# APP_1_ADC_m.net
KiCad netlist of a schematic drawn in Altium Designer
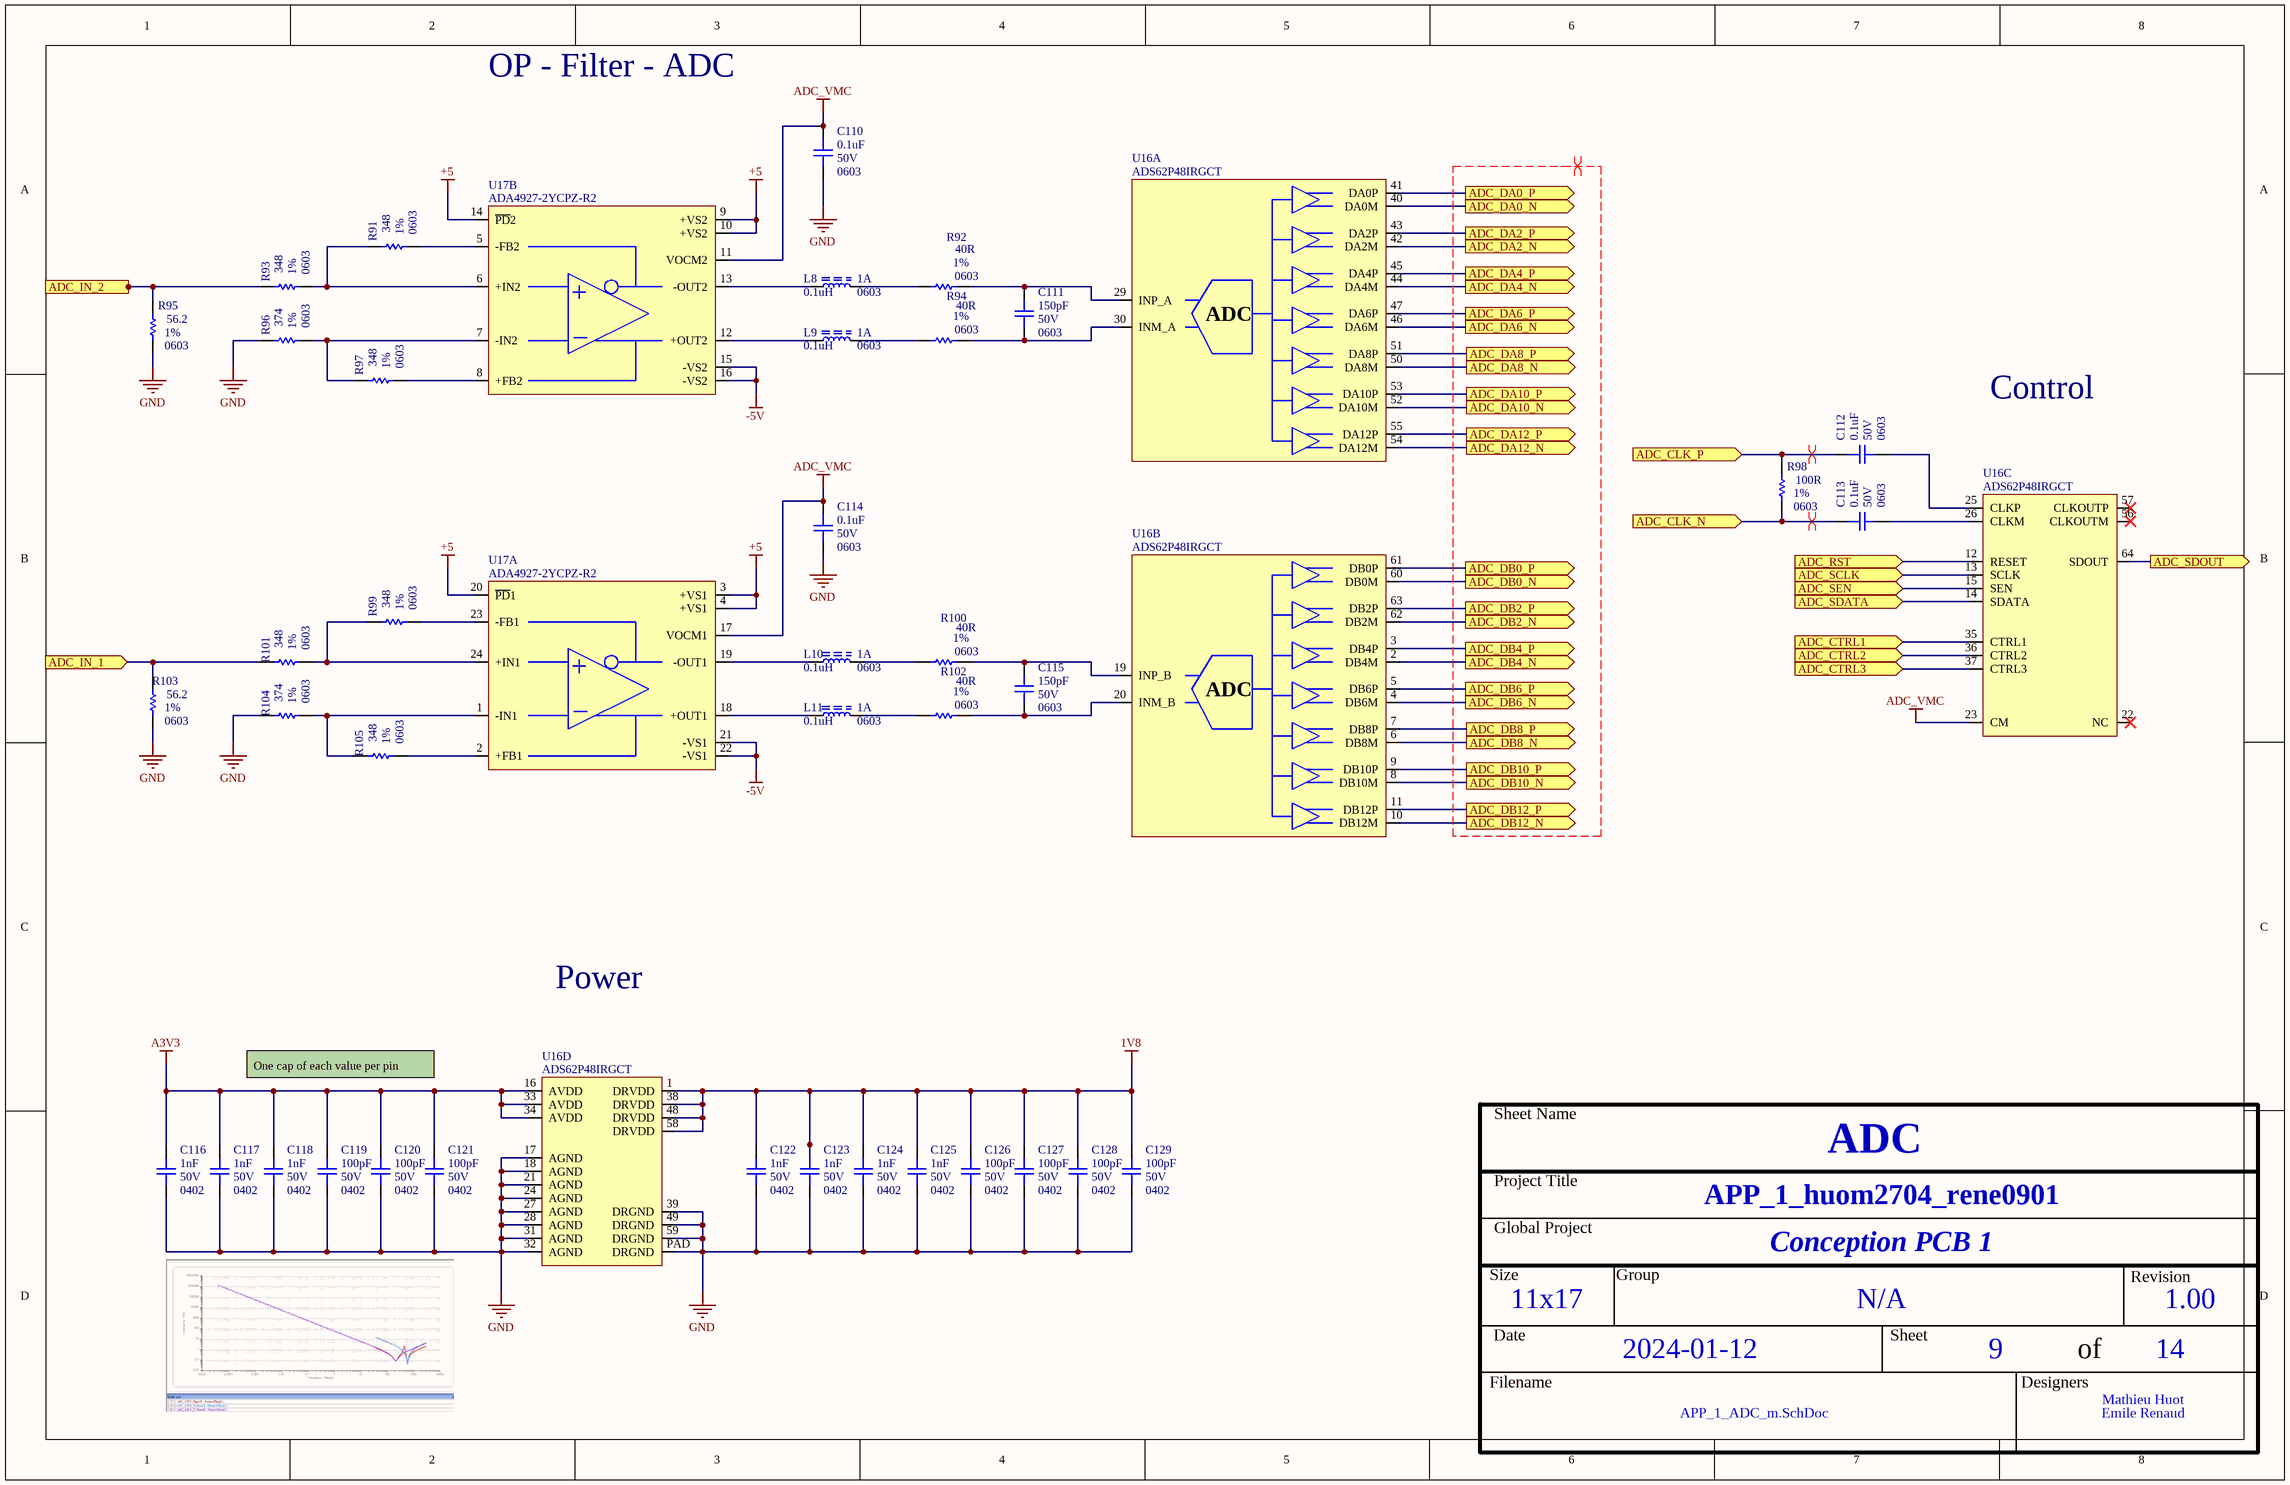
[diagram p0: APP_1_ADC_m.SchDoc]

(export (version "E")
  (design (tool "Eeschema 10.0.6"))
  (components
    (comp (ref "C110")
      (value "0.1uF")
      (footprint "CAP_0603")
      (description "CAP - 0603")
      (fields
        (field (name "VOLTAGE") "50V")
        (field (name "PACKAGE") "0603")
        (field (name "CREATEDBY") "Jonathan Bouchard")
      )
      (libsource (lib "S7CAS_LIB2023") (part "CAP - 0603"))
    )
    (comp (ref "C111")
      (value "150pF")
      (footprint "CAP_0603")
      (description "CAP - 0603")
      (fields
        (field (name "VOLTAGE") "50V")
        (field (name "PACKAGE") "0603")
        (field (name "CREATEDBY") "Jonathan Bouchard")
      )
      (libsource (lib "S7CAS_LIB2023") (part "CAP - 0603"))
    )
    (comp (ref "C112")
      (value "0.1uF")
      (footprint "CAP_0603")
      (description "CAP - 0603")
      (fields
        (field (name "VOLTAGE") "50V")
        (field (name "PACKAGE") "0603")
        (field (name "CREATEDBY") "Jonathan Bouchard")
      )
      (libsource (lib "S7CAS_LIB2023") (part "CAP - 0603"))
    )
    (comp (ref "C113")
      (value "0.1uF")
      (footprint "CAP_0603")
      (description "CAP - 0603")
      (fields
        (field (name "VOLTAGE") "50V")
        (field (name "PACKAGE") "0603")
        (field (name "CREATEDBY") "Jonathan Bouchard")
      )
      (libsource (lib "S7CAS_LIB2023") (part "CAP - 0603"))
    )
    (comp (ref "C114")
      (value "0.1uF")
      (footprint "CAP_0603")
      (description "CAP - 0603")
      (fields
        (field (name "VOLTAGE") "50V")
        (field (name "PACKAGE") "0603")
        (field (name "CREATEDBY") "Jonathan Bouchard")
      )
      (libsource (lib "S7CAS_LIB2023") (part "CAP - 0603"))
    )
    (comp (ref "C115")
      (value "150pF")
      (footprint "CAP_0603")
      (description "CAP - 0603")
      (fields
        (field (name "VOLTAGE") "50V")
        (field (name "PACKAGE") "0603")
        (field (name "CREATEDBY") "Jonathan Bouchard")
      )
      (libsource (lib "S7CAS_LIB2023") (part "CAP - 0603"))
    )
    (comp (ref "C116")
      (value "1nF")
      (footprint "CAP_0402")
      (description "CAP - 0402")
      (fields
        (field (name "VOLTAGE") "50V")
        (field (name "PACKAGE") "0402")
        (field (name "CREATEDBY") "Jonathan Bouchard")
      )
      (libsource (lib "S7CAS_LIB2023") (part "CAP - 0402"))
    )
    (comp (ref "C117")
      (value "1nF")
      (footprint "CAP_0402")
      (description "CAP - 0402")
      (fields
        (field (name "VOLTAGE") "50V")
        (field (name "PACKAGE") "0402")
        (field (name "CREATEDBY") "Jonathan Bouchard")
      )
      (libsource (lib "S7CAS_LIB2023") (part "CAP - 0402"))
    )
    (comp (ref "C118")
      (value "1nF")
      (footprint "CAP_0402")
      (description "CAP - 0402")
      (fields
        (field (name "VOLTAGE") "50V")
        (field (name "PACKAGE") "0402")
        (field (name "CREATEDBY") "Jonathan Bouchard")
      )
      (libsource (lib "S7CAS_LIB2023") (part "CAP - 0402"))
    )
    (comp (ref "C119")
      (value "100pF")
      (footprint "CAP_0402")
      (description "CAP - 0402")
      (fields
        (field (name "VOLTAGE") "50V")
        (field (name "PACKAGE") "0402")
        (field (name "CREATEDBY") "Jonathan Bouchard")
      )
      (libsource (lib "S7CAS_LIB2023") (part "CAP - 0402"))
    )
    (comp (ref "C120")
      (value "100pF")
      (footprint "CAP_0402")
      (description "CAP - 0402")
      (fields
        (field (name "VOLTAGE") "50V")
        (field (name "PACKAGE") "0402")
        (field (name "CREATEDBY") "Jonathan Bouchard")
      )
      (libsource (lib "S7CAS_LIB2023") (part "CAP - 0402"))
    )
    (comp (ref "C121")
      (value "100pF")
      (footprint "CAP_0402")
      (description "CAP - 0402")
      (fields
        (field (name "VOLTAGE") "50V")
        (field (name "PACKAGE") "0402")
        (field (name "CREATEDBY") "Jonathan Bouchard")
      )
      (libsource (lib "S7CAS_LIB2023") (part "CAP - 0402"))
    )
    (comp (ref "C122")
      (value "1nF")
      (footprint "CAP_0402")
      (description "CAP - 0402")
      (fields
        (field (name "VOLTAGE") "50V")
        (field (name "PACKAGE") "0402")
        (field (name "CREATEDBY") "Jonathan Bouchard")
      )
      (libsource (lib "S7CAS_LIB2023") (part "CAP - 0402"))
    )
    (comp (ref "C123")
      (value "1nF")
      (footprint "CAP_0402")
      (description "CAP - 0402")
      (fields
        (field (name "VOLTAGE") "50V")
        (field (name "PACKAGE") "0402")
        (field (name "CREATEDBY") "Jonathan Bouchard")
      )
      (libsource (lib "S7CAS_LIB2023") (part "CAP - 0402"))
    )
    (comp (ref "C124")
      (value "1nF")
      (footprint "CAP_0402")
      (description "CAP - 0402")
      (fields
        (field (name "VOLTAGE") "50V")
        (field (name "PACKAGE") "0402")
        (field (name "CREATEDBY") "Jonathan Bouchard")
      )
      (libsource (lib "S7CAS_LIB2023") (part "CAP - 0402"))
    )
    (comp (ref "C125")
      (value "1nF")
      (footprint "CAP_0402")
      (description "CAP - 0402")
      (fields
        (field (name "VOLTAGE") "50V")
        (field (name "PACKAGE") "0402")
        (field (name "CREATEDBY") "Jonathan Bouchard")
      )
      (libsource (lib "S7CAS_LIB2023") (part "CAP - 0402"))
    )
    (comp (ref "C126")
      (value "100pF")
      (footprint "CAP_0402")
      (description "CAP - 0402")
      (fields
        (field (name "VOLTAGE") "50V")
        (field (name "PACKAGE") "0402")
        (field (name "CREATEDBY") "Jonathan Bouchard")
      )
      (libsource (lib "S7CAS_LIB2023") (part "CAP - 0402"))
    )
    (comp (ref "C127")
      (value "100pF")
      (footprint "CAP_0402")
      (description "CAP - 0402")
      (fields
        (field (name "VOLTAGE") "50V")
        (field (name "PACKAGE") "0402")
        (field (name "CREATEDBY") "Jonathan Bouchard")
      )
      (libsource (lib "S7CAS_LIB2023") (part "CAP - 0402"))
    )
    (comp (ref "C128")
      (value "100pF")
      (footprint "CAP_0402")
      (description "CAP - 0402")
      (fields
        (field (name "VOLTAGE") "50V")
        (field (name "PACKAGE") "0402")
        (field (name "CREATEDBY") "Jonathan Bouchard")
      )
      (libsource (lib "S7CAS_LIB2023") (part "CAP - 0402"))
    )
    (comp (ref "C129")
      (value "100pF")
      (footprint "CAP_0402")
      (description "CAP - 0402")
      (fields
        (field (name "VOLTAGE") "50V")
        (field (name "PACKAGE") "0402")
        (field (name "CREATEDBY") "Jonathan Bouchard")
      )
      (libsource (lib "S7CAS_LIB2023") (part "CAP - 0402"))
    )
    (comp (ref "L8")
      (value "0.1uH")
      (footprint "FER_0603")
      (description "FER - 0603")
      (fields
        (field (name "CURRENT") "1A")
        (field (name "PACKAGE") "0603")
        (field (name "CREATEDBY") "Jonathan Bouchard")
      )
      (libsource (lib "S7CAS_LIB2023") (part "FER - 0603"))
    )
    (comp (ref "L9")
      (value "0.1uH")
      (footprint "FER_0603")
      (description "FER - 0603")
      (fields
        (field (name "CURRENT") "1A")
        (field (name "PACKAGE") "0603")
        (field (name "CREATEDBY") "Jonathan Bouchard")
      )
      (libsource (lib "S7CAS_LIB2023") (part "FER - 0603"))
    )
    (comp (ref "L10")
      (value "0.1uH")
      (footprint "FER_0603")
      (description "FER - 0603")
      (fields
        (field (name "CURRENT") "1A")
        (field (name "PACKAGE") "0603")
        (field (name "CREATEDBY") "Jonathan Bouchard")
      )
      (libsource (lib "S7CAS_LIB2023") (part "FER - 0603"))
    )
    (comp (ref "L11")
      (value "0.1uH")
      (footprint "FER_0603")
      (description "FER - 0603")
      (fields
        (field (name "CURRENT") "1A")
        (field (name "PACKAGE") "0603")
        (field (name "CREATEDBY") "Jonathan Bouchard")
      )
      (libsource (lib "S7CAS_LIB2023") (part "FER - 0603"))
    )
    (comp (ref "R91")
      (value "348")
      (footprint "RES_0603")
      (description "RES - 0603")
      (fields
        (field (name "PACKAGE") "0603")
        (field (name "PRECISION") "1%")
        (field (name "CREATEDBY") "Jonathan Bouchard")
      )
      (libsource (lib "S7CAS_LIB2023") (part "RES - 0603"))
    )
    (comp (ref "R92")
      (value "40R")
      (footprint "RES_0603")
      (description "RES - 0603")
      (fields
        (field (name "PACKAGE") "0603")
        (field (name "PRECISION") "1%")
        (field (name "CREATEDBY") "Jonathan Bouchard")
      )
      (libsource (lib "S7CAS_LIB2023") (part "RES - 0603"))
    )
    (comp (ref "R93")
      (value "348")
      (footprint "RES_0603")
      (description "RES - 0603")
      (fields
        (field (name "PACKAGE") "0603")
        (field (name "PRECISION") "1%")
        (field (name "CREATEDBY") "Jonathan Bouchard")
      )
      (libsource (lib "S7CAS_LIB2023") (part "RES - 0603"))
    )
    (comp (ref "R94")
      (value "40R")
      (footprint "RES_0603")
      (description "RES - 0603")
      (fields
        (field (name "PACKAGE") "0603")
        (field (name "PRECISION") "1%")
        (field (name "CREATEDBY") "Jonathan Bouchard")
      )
      (libsource (lib "S7CAS_LIB2023") (part "RES - 0603"))
    )
    (comp (ref "R95")
      (value "56.2")
      (footprint "RES_0603")
      (description "RES - 0603")
      (fields
        (field (name "PACKAGE") "0603")
        (field (name "PRECISION") "1%")
        (field (name "CREATEDBY") "Jonathan Bouchard")
      )
      (libsource (lib "S7CAS_LIB2023") (part "RES - 0603"))
    )
    (comp (ref "R96")
      (value "374")
      (footprint "RES_0603")
      (description "RES - 0603")
      (fields
        (field (name "PACKAGE") "0603")
        (field (name "PRECISION") "1%")
        (field (name "CREATEDBY") "Jonathan Bouchard")
      )
      (libsource (lib "S7CAS_LIB2023") (part "RES - 0603"))
    )
    (comp (ref "R97")
      (value "348")
      (footprint "RES_0603")
      (description "RES - 0603")
      (fields
        (field (name "PACKAGE") "0603")
        (field (name "PRECISION") "1%")
        (field (name "CREATEDBY") "Jonathan Bouchard")
      )
      (libsource (lib "S7CAS_LIB2023") (part "RES - 0603"))
    )
    (comp (ref "R98")
      (value "100R")
      (footprint "RES_0603")
      (description "RES - 0603")
      (fields
        (field (name "PACKAGE") "0603")
        (field (name "PRECISION") "1%")
        (field (name "CREATEDBY") "Jonathan Bouchard")
      )
      (libsource (lib "S7CAS_LIB2023") (part "RES - 0603"))
    )
    (comp (ref "R99")
      (value "348")
      (footprint "RES_0603")
      (description "RES - 0603")
      (fields
        (field (name "PACKAGE") "0603")
        (field (name "PRECISION") "1%")
        (field (name "CREATEDBY") "Jonathan Bouchard")
      )
      (libsource (lib "S7CAS_LIB2023") (part "RES - 0603"))
    )
    (comp (ref "R100")
      (value "40R")
      (footprint "RES_0603")
      (description "RES - 0603")
      (fields
        (field (name "PACKAGE") "0603")
        (field (name "PRECISION") "1%")
        (field (name "CREATEDBY") "Jonathan Bouchard")
      )
      (libsource (lib "S7CAS_LIB2023") (part "RES - 0603"))
    )
    (comp (ref "R101")
      (value "348")
      (footprint "RES_0603")
      (description "RES - 0603")
      (fields
        (field (name "PACKAGE") "0603")
        (field (name "PRECISION") "1%")
        (field (name "CREATEDBY") "Jonathan Bouchard")
      )
      (libsource (lib "S7CAS_LIB2023") (part "RES - 0603"))
    )
    (comp (ref "R102")
      (value "40R")
      (footprint "RES_0603")
      (description "RES - 0603")
      (fields
        (field (name "PACKAGE") "0603")
        (field (name "PRECISION") "1%")
        (field (name "CREATEDBY") "Jonathan Bouchard")
      )
      (libsource (lib "S7CAS_LIB2023") (part "RES - 0603"))
    )
    (comp (ref "R103")
      (value "56.2")
      (footprint "RES_0603")
      (description "RES - 0603")
      (fields
        (field (name "PACKAGE") "0603")
        (field (name "PRECISION") "1%")
        (field (name "CREATEDBY") "Jonathan Bouchard")
      )
      (libsource (lib "S7CAS_LIB2023") (part "RES - 0603"))
    )
    (comp (ref "R104")
      (value "374")
      (footprint "RES_0603")
      (description "RES - 0603")
      (fields
        (field (name "PACKAGE") "0603")
        (field (name "PRECISION") "1%")
        (field (name "CREATEDBY") "Jonathan Bouchard")
      )
      (libsource (lib "S7CAS_LIB2023") (part "RES - 0603"))
    )
    (comp (ref "R105")
      (value "348")
      (footprint "RES_0603")
      (description "RES - 0603")
      (fields
        (field (name "PACKAGE") "0603")
        (field (name "PRECISION") "1%")
        (field (name "CREATEDBY") "Jonathan Bouchard")
      )
      (libsource (lib "S7CAS_LIB2023") (part "RES - 0603"))
    )
    (comp (ref "U16")
      (value "ADS62P48IRGCT")
      (footprint "ADC_ADS62P48IRGCT")
      (description "ADC - 14 BIT 210MSPS SUAL - VQFN-64")
      (fields
        (field (name "VOLTAGE") "3.15 V ~ 3.6 V / 1.7 V ~ 1.9 V")
        (field (name "MFG") "Texas Instruments")
        (field (name "CREATEDBY") "Jonathan Bouchard")
      )
      (libsource (lib "S7CAS_LIB2023") (part "ADC_ADS62P48IRGCT"))
    )
    (comp (ref "U17")
      (value "ADA4927-2YCPZ-R2")
      (footprint "OPAMP_ADA4927-2YCPZ-R2")
      (description "OPAMP - CFA 2.3GHZ - QFN-24")
      (fields
        (field (name "VOLTAGE") "4.5 V ~ 11 V, ±2.25 V ~ 5.5 V")
        (field (name "MFG") "Analog Devices")
        (field (name "CREATEDBY") "Jonathan Bouchard")
      )
      (libsource (lib "S7CAS_LIB2023") (part "OPAMP_ADA4927-2YCPZ-R2"))
    )
  )
  (nets
    (net (code "1") (name "+5") (class "Default")
      (node (ref "U17") (pin "10") (pinfunction "+VS2_10") (pintype "passive"))
      (node (ref "U17") (pin "14") (pinfunction "~{PD}2_14") (pintype "passive"))
      (node (ref "U17") (pin "20") (pinfunction "~{PD}1_20") (pintype "passive"))
      (node (ref "U17") (pin "3") (pinfunction "+VS1_3") (pintype "passive"))
      (node (ref "U17") (pin "4") (pinfunction "+VS1_4") (pintype "passive"))
      (node (ref "U17") (pin "9") (pinfunction "+VS2_9") (pintype "passive"))
    )
    (net (code "2") (name "-5V") (class "Default")
      (node (ref "U17") (pin "15") (pinfunction "-VS2_15") (pintype "passive"))
      (node (ref "U17") (pin "16") (pinfunction "-VS2_16") (pintype "passive"))
      (node (ref "U17") (pin "21") (pinfunction "-VS1_21") (pintype "passive"))
      (node (ref "U17") (pin "22") (pinfunction "-VS1_22") (pintype "passive"))
    )
    (net (code "3") (name "/ADC_CLK_N") (class "Default")
      (node (ref "C113") (pin "2") (pinfunction "2_2") (pintype "passive"))
      (node (ref "R98") (pin "1") (pinfunction "1_1") (pintype "passive"))
    )
    (net (code "4") (name "/ADC_CLK_P") (class "Default")
      (node (ref "C112") (pin "2") (pinfunction "2_2") (pintype "passive"))
      (node (ref "R98") (pin "2") (pinfunction "2_2") (pintype "passive"))
    )
    (net (code "5") (name "/ADC_CTRL1") (class "Default")
      (node (ref "U16") (pin "35") (pinfunction "CTRL1_35") (pintype "passive"))
    )
    (net (code "6") (name "/ADC_CTRL2") (class "Default")
      (node (ref "U16") (pin "36") (pinfunction "CTRL2_36") (pintype "passive"))
    )
    (net (code "7") (name "/ADC_CTRL3") (class "Default")
      (node (ref "U16") (pin "37") (pinfunction "CTRL3_37") (pintype "passive"))
    )
    (net (code "8") (name "/ADC_DA0_N") (class "Default")
      (node (ref "U16") (pin "40") (pinfunction "DA0M_40") (pintype "passive"))
    )
    (net (code "9") (name "/ADC_DA0_P") (class "Default")
      (node (ref "U16") (pin "41") (pinfunction "DA0P_41") (pintype "passive"))
    )
    (net (code "10") (name "/ADC_DA2_N") (class "Default")
      (node (ref "U16") (pin "42") (pinfunction "DA2M_42") (pintype "passive"))
    )
    (net (code "11") (name "/ADC_DA2_P") (class "Default")
      (node (ref "U16") (pin "43") (pinfunction "DA2P_43") (pintype "passive"))
    )
    (net (code "12") (name "/ADC_DA4_N") (class "Default")
      (node (ref "U16") (pin "44") (pinfunction "DA4M_44") (pintype "passive"))
    )
    (net (code "13") (name "/ADC_DA4_P") (class "Default")
      (node (ref "U16") (pin "45") (pinfunction "DA4P_45") (pintype "passive"))
    )
    (net (code "14") (name "/ADC_DA6_N") (class "Default")
      (node (ref "U16") (pin "46") (pinfunction "DA6M_46") (pintype "passive"))
    )
    (net (code "15") (name "/ADC_DA6_P") (class "Default")
      (node (ref "U16") (pin "47") (pinfunction "DA6P_47") (pintype "passive"))
    )
    (net (code "16") (name "/ADC_DA8_N") (class "Default")
      (node (ref "U16") (pin "50") (pinfunction "DA8M_50") (pintype "passive"))
    )
    (net (code "17") (name "/ADC_DA8_P") (class "Default")
      (node (ref "U16") (pin "51") (pinfunction "DA8P_51") (pintype "passive"))
    )
    (net (code "18") (name "/ADC_DA10_N") (class "Default")
      (node (ref "U16") (pin "52") (pinfunction "DA10M_52") (pintype "passive"))
    )
    (net (code "19") (name "/ADC_DA10_P") (class "Default")
      (node (ref "U16") (pin "53") (pinfunction "DA10P_53") (pintype "passive"))
    )
    (net (code "20") (name "/ADC_DA12_N") (class "Default")
      (node (ref "U16") (pin "54") (pinfunction "DA12M_54") (pintype "passive"))
    )
    (net (code "21") (name "/ADC_DA12_P") (class "Default")
      (node (ref "U16") (pin "55") (pinfunction "DA12P_55") (pintype "passive"))
    )
    (net (code "22") (name "/ADC_DB0_N") (class "Default")
      (node (ref "U16") (pin "60") (pinfunction "DB0M_60") (pintype "passive"))
    )
    (net (code "23") (name "/ADC_DB0_P") (class "Default")
      (node (ref "U16") (pin "61") (pinfunction "DB0P_61") (pintype "passive"))
    )
    (net (code "24") (name "/ADC_DB2_N") (class "Default")
      (node (ref "U16") (pin "62") (pinfunction "DB2M_62") (pintype "passive"))
    )
    (net (code "25") (name "/ADC_DB2_P") (class "Default")
      (node (ref "U16") (pin "63") (pinfunction "DB2P_63") (pintype "passive"))
    )
    (net (code "26") (name "/ADC_DB4_N") (class "Default")
      (node (ref "U16") (pin "2") (pinfunction "DB4M_2") (pintype "passive"))
    )
    (net (code "27") (name "/ADC_DB4_P") (class "Default")
      (node (ref "U16") (pin "3") (pinfunction "DB4P_3") (pintype "passive"))
    )
    (net (code "28") (name "/ADC_DB6_N") (class "Default")
      (node (ref "U16") (pin "4") (pinfunction "DB6M_4") (pintype "passive"))
    )
    (net (code "29") (name "/ADC_DB6_P") (class "Default")
      (node (ref "U16") (pin "5") (pinfunction "DB6P_5") (pintype "passive"))
    )
    (net (code "30") (name "/ADC_DB8_N") (class "Default")
      (node (ref "U16") (pin "6") (pinfunction "DB8M_6") (pintype "passive"))
    )
    (net (code "31") (name "/ADC_DB8_P") (class "Default")
      (node (ref "U16") (pin "7") (pinfunction "DB8P_7") (pintype "passive"))
    )
    (net (code "32") (name "/ADC_DB10_N") (class "Default")
      (node (ref "U16") (pin "8") (pinfunction "DB10M_8") (pintype "passive"))
    )
    (net (code "33") (name "/ADC_DB10_P") (class "Default")
      (node (ref "U16") (pin "9") (pinfunction "DB10P_9") (pintype "passive"))
    )
    (net (code "34") (name "/ADC_DB12_N") (class "Default")
      (node (ref "U16") (pin "10") (pinfunction "DB12M_10") (pintype "passive"))
    )
    (net (code "35") (name "/ADC_DB12_P") (class "Default")
      (node (ref "U16") (pin "11") (pinfunction "DB12P_11") (pintype "passive"))
    )
    (net (code "36") (name "/ADC_IN_1") (class "Default")
      (node (ref "R101") (pin "2") (pinfunction "2_2") (pintype "passive"))
      (node (ref "R103") (pin "2") (pinfunction "2_2") (pintype "passive"))
    )
    (net (code "37") (name "/ADC_IN_2") (class "Default")
      (node (ref "R93") (pin "2") (pinfunction "2_2") (pintype "passive"))
      (node (ref "R95") (pin "2") (pinfunction "2_2") (pintype "passive"))
    )
    (net (code "38") (name "/ADC_RST") (class "Default")
      (node (ref "U16") (pin "12") (pinfunction "RESET_12") (pintype "passive"))
    )
    (net (code "39") (name "/ADC_SCLK") (class "Default")
      (node (ref "U16") (pin "13") (pinfunction "SCLK_13") (pintype "passive"))
    )
    (net (code "40") (name "/ADC_SDATA") (class "Default")
      (node (ref "U16") (pin "14") (pinfunction "SDATA_14") (pintype "passive"))
    )
    (net (code "41") (name "/ADC_SDOUT") (class "Default")
      (node (ref "U16") (pin "64") (pinfunction "SDOUT_64") (pintype "passive"))
    )
    (net (code "42") (name "/ADC_SEN") (class "Default")
      (node (ref "U16") (pin "15") (pinfunction "SEN_15") (pintype "passive"))
    )
    (net (code "43") (name "1V8") (class "Default")
      (node (ref "C122") (pin "2") (pinfunction "2_2") (pintype "passive"))
      (node (ref "C123") (pin "2") (pinfunction "2_2") (pintype "passive"))
      (node (ref "C124") (pin "2") (pinfunction "2_2") (pintype "passive"))
      (node (ref "C125") (pin "2") (pinfunction "2_2") (pintype "passive"))
      (node (ref "C126") (pin "2") (pinfunction "2_2") (pintype "passive"))
      (node (ref "C127") (pin "2") (pinfunction "2_2") (pintype "passive"))
      (node (ref "C128") (pin "2") (pinfunction "2_2") (pintype "passive"))
      (node (ref "C129") (pin "2") (pinfunction "2_2") (pintype "passive"))
      (node (ref "U16") (pin "1") (pinfunction "DRVDD_1") (pintype "passive"))
      (node (ref "U16") (pin "38") (pinfunction "DRVDD_38") (pintype "passive"))
      (node (ref "U16") (pin "48") (pinfunction "DRVDD_48") (pintype "passive"))
      (node (ref "U16") (pin "58") (pinfunction "DRVDD_58") (pintype "passive"))
    )
    (net (code "44") (name "A3V3") (class "Default")
      (node (ref "C116") (pin "2") (pinfunction "2_2") (pintype "passive"))
      (node (ref "C117") (pin "2") (pinfunction "2_2") (pintype "passive"))
      (node (ref "C118") (pin "2") (pinfunction "2_2") (pintype "passive"))
      (node (ref "C119") (pin "2") (pinfunction "2_2") (pintype "passive"))
      (node (ref "C120") (pin "2") (pinfunction "2_2") (pintype "passive"))
      (node (ref "C121") (pin "2") (pinfunction "2_2") (pintype "passive"))
      (node (ref "U16") (pin "16") (pinfunction "AVDD_16") (pintype "passive"))
      (node (ref "U16") (pin "33") (pinfunction "AVDD_33") (pintype "passive"))
      (node (ref "U16") (pin "34") (pinfunction "AVDD_34") (pintype "passive"))
    )
    (net (code "45") (name "ADC_VMC") (class "Default")
      (node (ref "C110") (pin "2") (pinfunction "2_2") (pintype "passive"))
      (node (ref "C114") (pin "2") (pinfunction "2_2") (pintype "passive"))
      (node (ref "U16") (pin "23") (pinfunction "CM_23") (pintype "passive"))
      (node (ref "U17") (pin "11") (pinfunction "VOCM2_11") (pintype "passive"))
      (node (ref "U17") (pin "17") (pinfunction "VOCM1_17") (pintype "passive"))
    )
    (net (code "46") (name "GND") (class "Default")
      (node (ref "C110") (pin "1") (pinfunction "1_1") (pintype "passive"))
      (node (ref "C114") (pin "1") (pinfunction "1_1") (pintype "passive"))
      (node (ref "C116") (pin "1") (pinfunction "1_1") (pintype "passive"))
      (node (ref "C117") (pin "1") (pinfunction "1_1") (pintype "passive"))
      (node (ref "C118") (pin "1") (pinfunction "1_1") (pintype "passive"))
      (node (ref "C119") (pin "1") (pinfunction "1_1") (pintype "passive"))
      (node (ref "C120") (pin "1") (pinfunction "1_1") (pintype "passive"))
      (node (ref "C121") (pin "1") (pinfunction "1_1") (pintype "passive"))
      (node (ref "C122") (pin "1") (pinfunction "1_1") (pintype "passive"))
      (node (ref "C123") (pin "1") (pinfunction "1_1") (pintype "passive"))
      (node (ref "C124") (pin "1") (pinfunction "1_1") (pintype "passive"))
      (node (ref "C125") (pin "1") (pinfunction "1_1") (pintype "passive"))
      (node (ref "C126") (pin "1") (pinfunction "1_1") (pintype "passive"))
      (node (ref "C127") (pin "1") (pinfunction "1_1") (pintype "passive"))
      (node (ref "C128") (pin "1") (pinfunction "1_1") (pintype "passive"))
      (node (ref "C129") (pin "1") (pinfunction "1_1") (pintype "passive"))
      (node (ref "R103") (pin "1") (pinfunction "1_1") (pintype "passive"))
      (node (ref "R104") (pin "2") (pinfunction "2_2") (pintype "passive"))
      (node (ref "R95") (pin "1") (pinfunction "1_1") (pintype "passive"))
      (node (ref "R96") (pin "2") (pinfunction "2_2") (pintype "passive"))
      (node (ref "U16") (pin "17") (pinfunction "AGND_17") (pintype "passive"))
      (node (ref "U16") (pin "18") (pinfunction "AGND_18") (pintype "passive"))
      (node (ref "U16") (pin "21") (pinfunction "AGND_21") (pintype "passive"))
      (node (ref "U16") (pin "24") (pinfunction "AGND_24") (pintype "passive"))
      (node (ref "U16") (pin "27") (pinfunction "AGND_27") (pintype "passive"))
      (node (ref "U16") (pin "28") (pinfunction "AGND_28") (pintype "passive"))
      (node (ref "U16") (pin "31") (pinfunction "AGND_31") (pintype "passive"))
      (node (ref "U16") (pin "32") (pinfunction "AGND_32") (pintype "passive"))
      (node (ref "U16") (pin "39") (pinfunction "DRGND_39") (pintype "passive"))
      (node (ref "U16") (pin "49") (pinfunction "DRGND_49") (pintype "passive"))
      (node (ref "U16") (pin "59") (pinfunction "DRGND_59") (pintype "passive"))
      (node (ref "U16") (pin "PAD") (pinfunction "DRGND_PAD") (pintype "passive"))
    )
    (net (code "47") (name "Net-(L8-Pad1)") (class "Default")
      (node (ref "L8") (pin "1") (pinfunction "1_1") (pintype "passive"))
      (node (ref "R92") (pin "2") (pinfunction "2_2") (pintype "passive"))
    )
    (net (code "48") (name "Net-(L9-Pad1)") (class "Default")
      (node (ref "L9") (pin "1") (pinfunction "1_1") (pintype "passive"))
      (node (ref "R94") (pin "2") (pinfunction "2_2") (pintype "passive"))
    )
    (net (code "49") (name "Net-(L10-Pad1)") (class "Default")
      (node (ref "L10") (pin "1") (pinfunction "1_1") (pintype "passive"))
      (node (ref "R100") (pin "2") (pinfunction "2_2") (pintype "passive"))
    )
    (net (code "50") (name "Net-(L11-Pad1)") (class "Default")
      (node (ref "L11") (pin "1") (pinfunction "1_1") (pintype "passive"))
      (node (ref "R102") (pin "2") (pinfunction "2_2") (pintype "passive"))
    )
    (net (code "51") (name "Net-(U16A-INM_A)") (class "Default")
      (node (ref "C111") (pin "1") (pinfunction "1_1") (pintype "passive"))
      (node (ref "R94") (pin "1") (pinfunction "1_1") (pintype "passive"))
      (node (ref "U16") (pin "30") (pinfunction "INM_A_30") (pintype "passive"))
    )
    (net (code "52") (name "Net-(U16A-INP_A)") (class "Default")
      (node (ref "C111") (pin "2") (pinfunction "2_2") (pintype "passive"))
      (node (ref "R92") (pin "1") (pinfunction "1_1") (pintype "passive"))
      (node (ref "U16") (pin "29") (pinfunction "INP_A_29") (pintype "passive"))
    )
    (net (code "53") (name "Net-(U16B-INM_B)") (class "Default")
      (node (ref "C115") (pin "1") (pinfunction "1_1") (pintype "passive"))
      (node (ref "R102") (pin "1") (pinfunction "1_1") (pintype "passive"))
      (node (ref "U16") (pin "20") (pinfunction "INM_B_20") (pintype "passive"))
    )
    (net (code "54") (name "Net-(U16B-INP_B)") (class "Default")
      (node (ref "C115") (pin "2") (pinfunction "2_2") (pintype "passive"))
      (node (ref "R100") (pin "1") (pinfunction "1_1") (pintype "passive"))
      (node (ref "U16") (pin "19") (pinfunction "INP_B_19") (pintype "passive"))
    )
    (net (code "55") (name "Net-(U16C-CLKM)") (class "Default")
      (node (ref "C113") (pin "1") (pinfunction "1_1") (pintype "passive"))
      (node (ref "U16") (pin "26") (pinfunction "CLKM_26") (pintype "passive"))
    )
    (net (code "56") (name "Net-(U16C-CLKP)") (class "Default")
      (node (ref "C112") (pin "1") (pinfunction "1_1") (pintype "passive"))
      (node (ref "U16") (pin "25") (pinfunction "CLKP_25") (pintype "passive"))
    )
    (net (code "57") (name "Net-(U17A-+FB1)") (class "Default")
      (node (ref "R105") (pin "1") (pinfunction "1_1") (pintype "passive"))
      (node (ref "U17") (pin "2") (pinfunction "+FB1_2") (pintype "passive"))
    )
    (net (code "58") (name "Net-(U17A-+IN1)") (class "Default")
      (node (ref "R101") (pin "1") (pinfunction "1_1") (pintype "passive"))
      (node (ref "R99") (pin "2") (pinfunction "2_2") (pintype "passive"))
      (node (ref "U17") (pin "24") (pinfunction "+IN1_24") (pintype "passive"))
    )
    (net (code "59") (name "Net-(U17A-+OUT1)") (class "Default")
      (node (ref "L11") (pin "2") (pinfunction "2_2") (pintype "passive"))
      (node (ref "U17") (pin "18") (pinfunction "+OUT1_18") (pintype "passive"))
    )
    (net (code "60") (name "Net-(U17A--FB1)") (class "Default")
      (node (ref "R99") (pin "1") (pinfunction "1_1") (pintype "passive"))
      (node (ref "U17") (pin "23") (pinfunction "-FB1_23") (pintype "passive"))
    )
    (net (code "61") (name "Net-(U17A--IN1)") (class "Default")
      (node (ref "R104") (pin "1") (pinfunction "1_1") (pintype "passive"))
      (node (ref "R105") (pin "2") (pinfunction "2_2") (pintype "passive"))
      (node (ref "U17") (pin "1") (pinfunction "-IN1_1") (pintype "passive"))
    )
    (net (code "62") (name "Net-(U17A--OUT1)") (class "Default")
      (node (ref "L10") (pin "2") (pinfunction "2_2") (pintype "passive"))
      (node (ref "U17") (pin "19") (pinfunction "-OUT1_19") (pintype "passive"))
    )
    (net (code "63") (name "Net-(U17B-+FB2)") (class "Default")
      (node (ref "R97") (pin "1") (pinfunction "1_1") (pintype "passive"))
      (node (ref "U17") (pin "8") (pinfunction "+FB2_8") (pintype "passive"))
    )
    (net (code "64") (name "Net-(U17B-+IN2)") (class "Default")
      (node (ref "R91") (pin "2") (pinfunction "2_2") (pintype "passive"))
      (node (ref "R93") (pin "1") (pinfunction "1_1") (pintype "passive"))
      (node (ref "U17") (pin "6") (pinfunction "+IN2_6") (pintype "passive"))
    )
    (net (code "65") (name "Net-(U17B-+OUT2)") (class "Default")
      (node (ref "L9") (pin "2") (pinfunction "2_2") (pintype "passive"))
      (node (ref "U17") (pin "12") (pinfunction "+OUT2_12") (pintype "passive"))
    )
    (net (code "66") (name "Net-(U17B--FB2)") (class "Default")
      (node (ref "R91") (pin "1") (pinfunction "1_1") (pintype "passive"))
      (node (ref "U17") (pin "5") (pinfunction "-FB2_5") (pintype "passive"))
    )
    (net (code "67") (name "Net-(U17B--IN2)") (class "Default")
      (node (ref "R96") (pin "1") (pinfunction "1_1") (pintype "passive"))
      (node (ref "R97") (pin "2") (pinfunction "2_2") (pintype "passive"))
      (node (ref "U17") (pin "7") (pinfunction "-IN2_7") (pintype "passive"))
    )
    (net (code "68") (name "Net-(U17B--OUT2)") (class "Default")
      (node (ref "L8") (pin "2") (pinfunction "2_2") (pintype "passive"))
      (node (ref "U17") (pin "13") (pinfunction "-OUT2_13") (pintype "passive"))
    )
    (net (code "69") (name "unconnected-(U16C-CLKOUTM-Pad56)") (class "Default")
      (node (ref "U16") (pin "56") (pinfunction "CLKOUTM_56") (pintype "passive+no_connect"))
    )
    (net (code "70") (name "unconnected-(U16C-CLKOUTP-Pad57)") (class "Default")
      (node (ref "U16") (pin "57") (pinfunction "CLKOUTP_57") (pintype "passive+no_connect"))
    )
    (net (code "71") (name "unconnected-(U16C-NC-Pad22)") (class "Default")
      (node (ref "U16") (pin "22") (pinfunction "NC_22") (pintype "passive+no_connect"))
    )
  )
)
